# SlotCar_v1_0_1.net
KiCad netlist of a schematic drawn in EAGLE
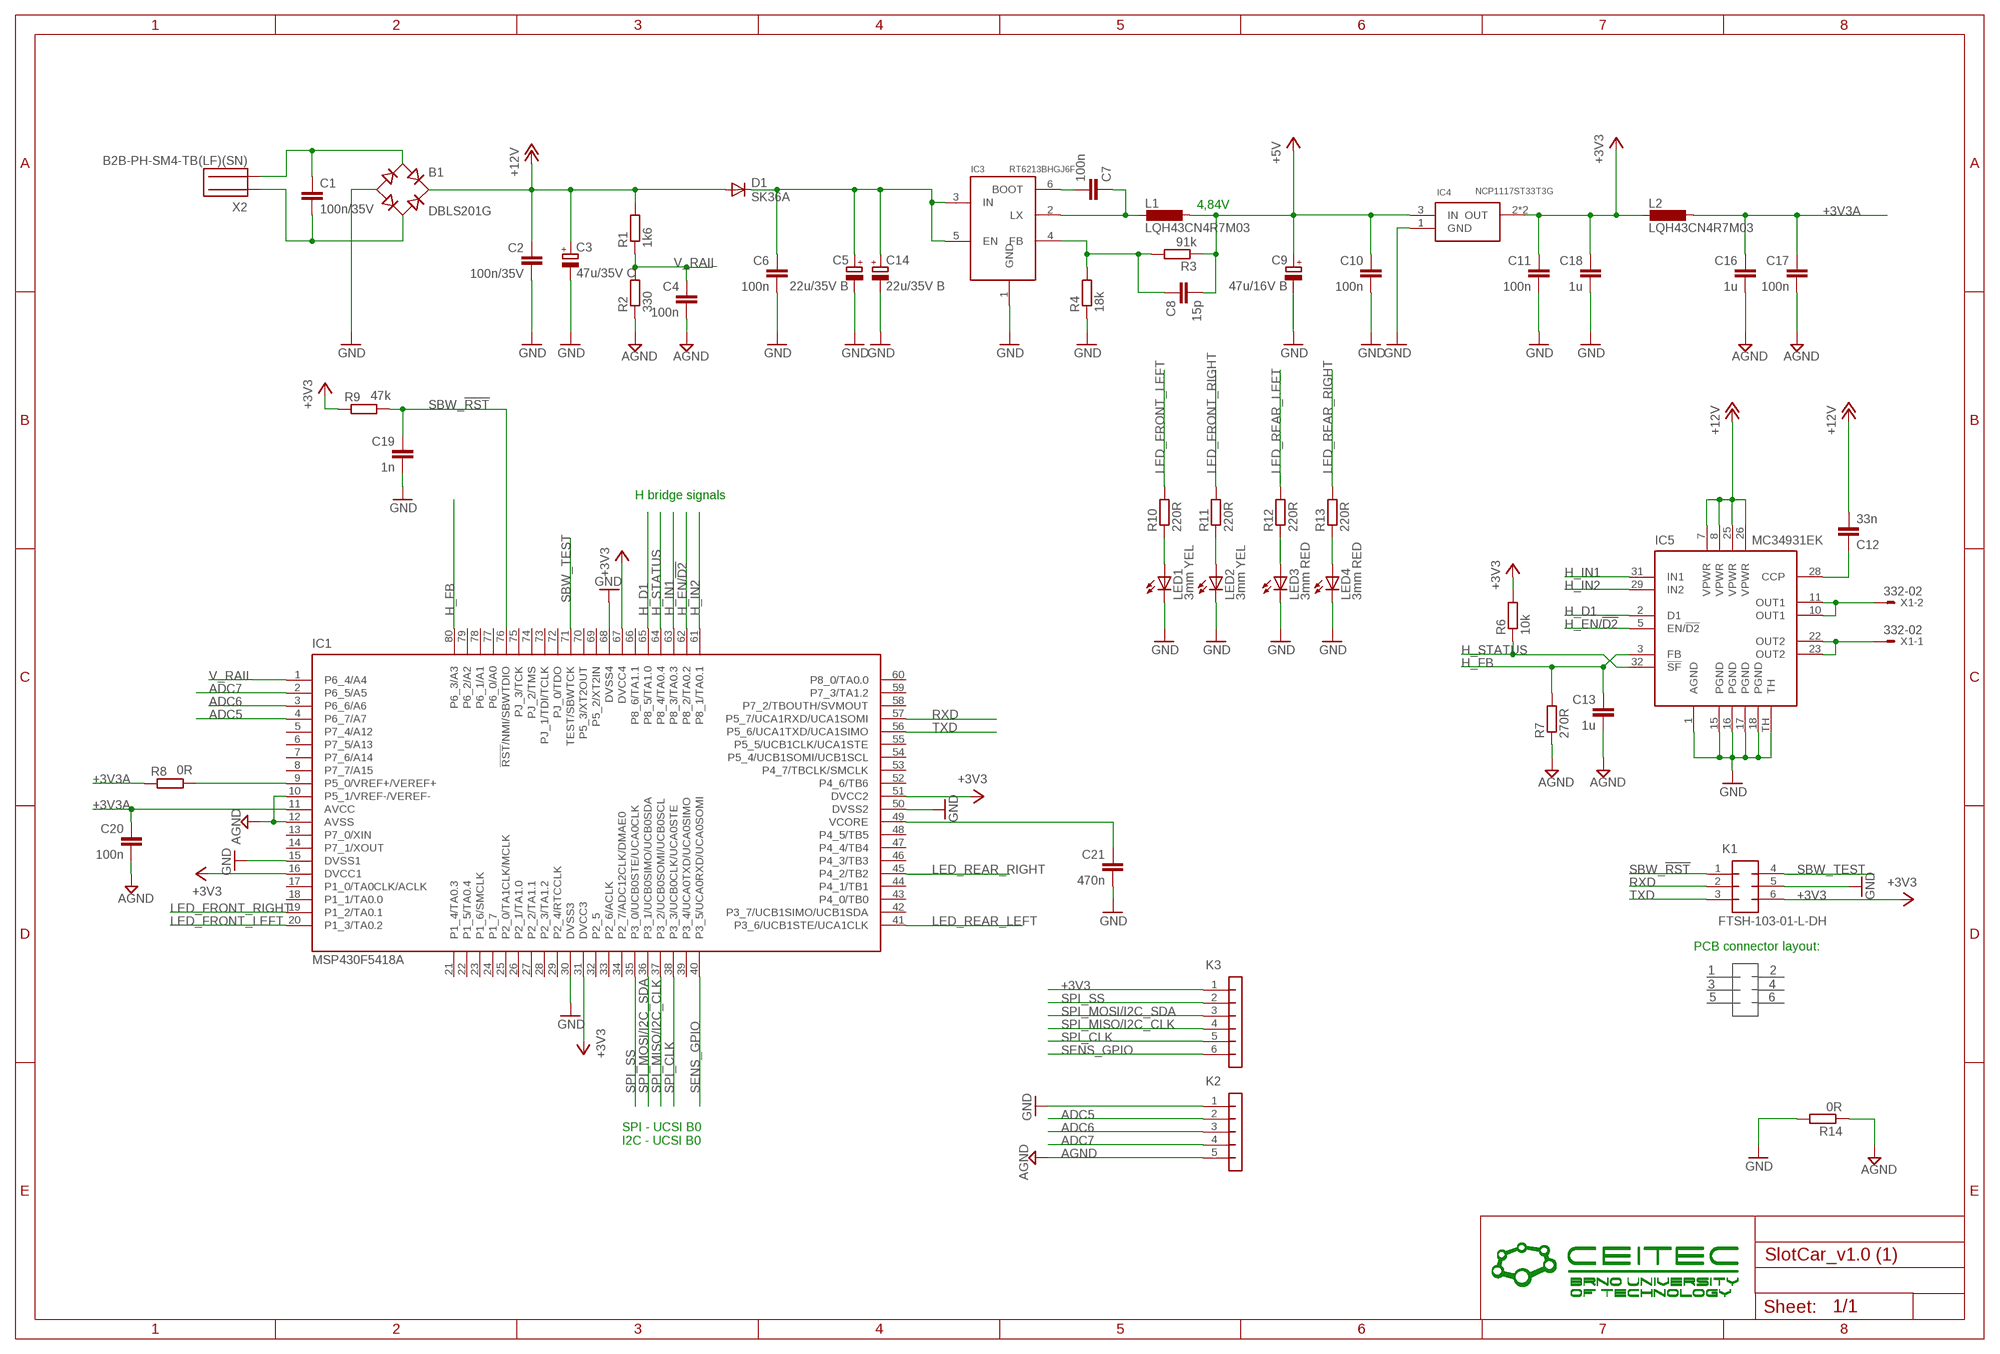
[diagram p0: schematic, sheet 1]

(export (version "E")
  (design (tool "Eeschema 10.0.6"))
  (components
    (comp (ref "B1")
      (value "DBLS201G")
      (footprint "eagle-import:DBS")
      (libsource (lib "eagle-import") (part "DB?GLS201"))
    )
    (comp (ref "C1")
      (value "100n/35V")
      (footprint "eagle-import:C0805K")
      (libsource (lib "eagle-import") (part "C-EUC0805K"))
    )
    (comp (ref "C2")
      (value "100n/35V")
      (footprint "eagle-import:C0805K")
      (libsource (lib "eagle-import") (part "C-EUC0805K"))
    )
    (comp (ref "C3")
      (value "47u/35V C")
      (footprint "eagle-import:153CLV-0505")
      (libsource (lib "eagle-import") (part "CPOL-EU153CLV-0505"))
    )
    (comp (ref "C4")
      (value "100n")
      (footprint "eagle-import:C0805K")
      (libsource (lib "eagle-import") (part "C-EUC0805K"))
    )
    (comp (ref "C5")
      (value "22u/35V B")
      (footprint "eagle-import:153CLV-0405")
      (libsource (lib "eagle-import") (part "CPOL-EU153CLV-0405"))
    )
    (comp (ref "C6")
      (value "100n")
      (footprint "eagle-import:C0805K")
      (libsource (lib "eagle-import") (part "C-EUC0805K"))
    )
    (comp (ref "C7")
      (value "100n")
      (footprint "eagle-import:C0805K")
      (libsource (lib "eagle-import") (part "C-EUC0805K"))
    )
    (comp (ref "C8")
      (value "15p")
      (footprint "eagle-import:C0805K")
      (libsource (lib "eagle-import") (part "C-EUC0805K"))
    )
    (comp (ref "C9")
      (value "47u/16V B")
      (footprint "eagle-import:153CLV-0405")
      (libsource (lib "eagle-import") (part "CPOL-EU153CLV-0405"))
    )
    (comp (ref "C10")
      (value "100n")
      (footprint "eagle-import:C0805K")
      (libsource (lib "eagle-import") (part "C-EUC0805K"))
    )
    (comp (ref "C11")
      (value "100n")
      (footprint "eagle-import:C0805K")
      (libsource (lib "eagle-import") (part "C-EUC0805K"))
    )
    (comp (ref "C12")
      (value "33n")
      (footprint "eagle-import:C0805K")
      (libsource (lib "eagle-import") (part "C-EUC0805K"))
    )
    (comp (ref "C13")
      (value "1u")
      (footprint "eagle-import:C0805K")
      (libsource (lib "eagle-import") (part "C-EUC0805K"))
    )
    (comp (ref "C14")
      (value "22u/35V B")
      (footprint "eagle-import:153CLV-0405")
      (libsource (lib "eagle-import") (part "CPOL-EU153CLV-0405"))
    )
    (comp (ref "C16")
      (value "1u")
      (footprint "eagle-import:C0805K")
      (libsource (lib "eagle-import") (part "C-EUC0805K"))
    )
    (comp (ref "C17")
      (value "100n")
      (footprint "eagle-import:C0805K")
      (libsource (lib "eagle-import") (part "C-EUC0805K"))
    )
    (comp (ref "C18")
      (value "1u")
      (footprint "eagle-import:C0805K")
      (libsource (lib "eagle-import") (part "C-EUC0805K"))
    )
    (comp (ref "C19")
      (value "1n")
      (footprint "eagle-import:C0805K")
      (libsource (lib "eagle-import") (part "C-EUC0805K"))
    )
    (comp (ref "C20")
      (value "100n")
      (footprint "eagle-import:C0805K")
      (libsource (lib "eagle-import") (part "C-EUC0805K"))
    )
    (comp (ref "C21")
      (value "470n")
      (footprint "eagle-import:C0805K")
      (libsource (lib "eagle-import") (part "C-EUC0805K"))
    )
    (comp (ref "D1")
      (value "SK36A")
      (footprint "eagle-import:DO214AC")
      (libsource (lib "eagle-import") (part "DIODE-DO214AC"))
    )
    (comp (ref "IC1")
      (value "MSP430F5418A")
      (footprint "eagle-import:PN_S-PQFP-G80")
      (fields (field (name "MPN") "MSP430F5418AIPN"))
      (libsource (lib "eagle-import") (part "MSP430F5418A"))
    )
    (comp (ref "IC3")
      (value "RT6213BHGJ6F")
      (footprint "eagle-import:SOT23-6")
      (libsource (lib "eagle-import") (part "RT6213BHGJ6F"))
    )
    (comp (ref "IC4")
      (value "NCP1117ST33T3G")
      (footprint "eagle-import:SOT223")
      (libsource (lib "eagle-import") (part "NCP1117ST33T3G"))
    )
    (comp (ref "IC5")
      (value "MC34931EK")
      (footprint "eagle-import:SOIC32W")
      (libsource (lib "eagle-import") (part "MC34931EK"))
    )
    (comp (ref "K1")
      (value "FTSH-103-01-L-DH")
      (footprint "eagle-import:PINHEAD_2X3_RM1.27")
      (libsource (lib "eagle-import") (part "FTSH-103-01-L-DH"))
    )
    (comp (ref "K2")
      (value "PIN_1X5_SMD")
      (footprint "eagle-import:PINHEAD_1X5_RM1.27SMD")
      (libsource (lib "eagle-import") (part "PIN_1X5_SMD"))
    )
    (comp (ref "K3")
      (value "PIN_1X6_SMD")
      (footprint "eagle-import:PINHEAD_1X6_RM1.27SMD")
      (libsource (lib "eagle-import") (part "PIN_1X6_SMD"))
    )
    (comp (ref "L1")
      (value "LQH43CN4R7M03")
      (footprint "eagle-import:L1812")
      (libsource (lib "eagle-import") (part "L-EUL1812"))
    )
    (comp (ref "L2")
      (value "LQH43CN4R7M03")
      (footprint "eagle-import:L1812")
      (libsource (lib "eagle-import") (part "L-EUL1812"))
    )
    (comp (ref "LED1")
      (value "3mm YEL")
      (footprint "eagle-import:LED3MM")
      (libsource (lib "eagle-import") (part "LED3MM"))
    )
    (comp (ref "LED2")
      (value "3mm YEL")
      (footprint "eagle-import:LED3MM")
      (libsource (lib "eagle-import") (part "LED3MM"))
    )
    (comp (ref "LED3")
      (value "3mm RED")
      (footprint "eagle-import:LED3MM")
      (libsource (lib "eagle-import") (part "LED3MM"))
    )
    (comp (ref "LED4")
      (value "3mm RED")
      (footprint "eagle-import:LED3MM")
      (libsource (lib "eagle-import") (part "LED3MM"))
    )
    (comp (ref "R1")
      (value "1k6")
      (footprint "eagle-import:M0805")
      (libsource (lib "eagle-import") (part "R-EU_M0805"))
    )
    (comp (ref "R2")
      (value "330")
      (footprint "eagle-import:M0805")
      (libsource (lib "eagle-import") (part "R-EU_M0805"))
    )
    (comp (ref "R3")
      (value "91k")
      (footprint "eagle-import:M0805")
      (libsource (lib "eagle-import") (part "R-EU_M0805"))
    )
    (comp (ref "R4")
      (value "18k")
      (footprint "eagle-import:M0805")
      (libsource (lib "eagle-import") (part "R-EU_M0805"))
    )
    (comp (ref "R6")
      (value "10k")
      (footprint "eagle-import:M0805")
      (libsource (lib "eagle-import") (part "R-EU_M0805"))
    )
    (comp (ref "R7")
      (value "270R")
      (footprint "eagle-import:M0805")
      (libsource (lib "eagle-import") (part "R-EU_M0805"))
    )
    (comp (ref "R8")
      (value "0R")
      (footprint "eagle-import:M0805")
      (libsource (lib "eagle-import") (part "R-EU_M0805"))
    )
    (comp (ref "R9")
      (value "47k")
      (footprint "eagle-import:M0805")
      (libsource (lib "eagle-import") (part "R-EU_M0805"))
    )
    (comp (ref "R10")
      (value "220R")
      (footprint "eagle-import:M0805")
      (libsource (lib "eagle-import") (part "R-EU_M0805"))
    )
    (comp (ref "R11")
      (value "220R")
      (footprint "eagle-import:M0805")
      (libsource (lib "eagle-import") (part "R-EU_M0805"))
    )
    (comp (ref "R12")
      (value "220R")
      (footprint "eagle-import:M0805")
      (libsource (lib "eagle-import") (part "R-EU_M0805"))
    )
    (comp (ref "R13")
      (value "220R")
      (footprint "eagle-import:M0805")
      (libsource (lib "eagle-import") (part "R-EU_M0805"))
    )
    (comp (ref "R14")
      (value "0R")
      (footprint "eagle-import:M0805")
      (libsource (lib "eagle-import") (part "R-EU_M0805"))
    )
    (comp (ref "X1")
      (value "332-02")
      (footprint "eagle-import:332-02")
      (libsource (lib "eagle-import") (part "332-02"))
    )
    (comp (ref "X2")
      (value "B2B-PH-SM4-TB(LF)(SN)")
      (footprint "eagle-import:JST-2.00MM-2P")
      (libsource (lib "eagle-import") (part "JST-2P-2.00MM-90DEG"))
    )
  )
  (nets
    (net (code "1") (name "+3V3") (class "Default")
      (node (ref "C11") (pin "1") (pinfunction "1_1") (pintype "passive"))
      (node (ref "C18") (pin "1") (pinfunction "1_1") (pintype "passive"))
      (node (ref "IC1") (pin "16") (pinfunction "DVCC1_16") (pintype "power_in"))
      (node (ref "IC1") (pin "31") (pinfunction "DVCC3_31") (pintype "power_in"))
      (node (ref "IC1") (pin "51") (pinfunction "DVCC2_51") (pintype "power_in"))
      (node (ref "IC1") (pin "67") (pinfunction "DVCC4_67") (pintype "power_in"))
      (node (ref "IC4") (pin "2") (pinfunction "OUT_2") (pintype "bidirectional"))
      (node (ref "IC4") (pin "4") (pinfunction "OUT_4") (pintype "bidirectional"))
      (node (ref "K1") (pin "6") (pinfunction "P$6_6") (pintype "bidirectional"))
      (node (ref "K3") (pin "1") (pinfunction "P$1_1") (pintype "bidirectional"))
      (node (ref "L2") (pin "2") (pinfunction "2_2") (pintype "passive"))
      (node (ref "R6") (pin "2") (pinfunction "2_2") (pintype "passive"))
      (node (ref "R9") (pin "1") (pinfunction "1_1") (pintype "passive"))
    )
    (net (code "2") (name "+5V") (class "Default")
      (node (ref "C10") (pin "1") (pinfunction "1_1") (pintype "passive"))
      (node (ref "C8") (pin "2") (pinfunction "2_2") (pintype "passive"))
      (node (ref "C9") (pin "+") (pinfunction "+_+") (pintype "passive"))
      (node (ref "IC4") (pin "3") (pinfunction "IN_3") (pintype "bidirectional"))
      (node (ref "L1") (pin "1") (pinfunction "1_1") (pintype "passive"))
      (node (ref "R3") (pin "1") (pinfunction "1_1") (pintype "passive"))
    )
    (net (code "3") (name "+12V") (class "Default")
      (node (ref "B1") (pin "+") (pinfunction "+_+") (pintype "passive"))
      (node (ref "C12") (pin "2") (pinfunction "2_2") (pintype "passive"))
      (node (ref "C2") (pin "1") (pinfunction "1_1") (pintype "passive"))
      (node (ref "C3") (pin "+") (pinfunction "+_+") (pintype "passive"))
      (node (ref "D1") (pin "A") (pinfunction "A_A") (pintype "passive"))
      (node (ref "IC5") (pin "25") (pinfunction "VPWR_25") (pintype "bidirectional"))
      (node (ref "IC5") (pin "26") (pinfunction "VPWR_26") (pintype "bidirectional"))
      (node (ref "IC5") (pin "7") (pinfunction "VPWR_7") (pintype "bidirectional"))
      (node (ref "IC5") (pin "8") (pinfunction "VPWR_8") (pintype "bidirectional"))
      (node (ref "R1") (pin "2") (pinfunction "2_2") (pintype "passive"))
    )
    (net (code "4") (name "/+3V3A") (class "Default")
      (node (ref "C16") (pin "1") (pinfunction "1_1") (pintype "passive"))
      (node (ref "C17") (pin "1") (pinfunction "1_1") (pintype "passive"))
      (node (ref "C20") (pin "1") (pinfunction "1_1") (pintype "passive"))
      (node (ref "IC1") (pin "11") (pinfunction "AVCC_11") (pintype "power_in"))
      (node (ref "L2") (pin "1") (pinfunction "1_1") (pintype "passive"))
      (node (ref "R8") (pin "1") (pinfunction "1_1") (pintype "passive"))
    )
    (net (code "5") (name "/ADC5") (class "Default")
      (node (ref "IC1") (pin "4") (pinfunction "P6_7/A7_4") (pintype "bidirectional"))
      (node (ref "K2") (pin "2") (pinfunction "P$2_2") (pintype "bidirectional"))
    )
    (net (code "6") (name "/ADC6") (class "Default")
      (node (ref "IC1") (pin "3") (pinfunction "P6_6/A6_3") (pintype "bidirectional"))
      (node (ref "K2") (pin "3") (pinfunction "P$3_3") (pintype "bidirectional"))
    )
    (net (code "7") (name "/ADC7") (class "Default")
      (node (ref "IC1") (pin "2") (pinfunction "P6_5/A5_2") (pintype "bidirectional"))
      (node (ref "K2") (pin "4") (pinfunction "P$4_4") (pintype "bidirectional"))
    )
    (net (code "8") (name "/H_D1") (class "Default")
      (node (ref "IC1") (pin "65") (pinfunction "P8_5/TA1.0_65") (pintype "bidirectional"))
      (node (ref "IC5") (pin "2") (pinfunction "D1_2") (pintype "bidirectional"))
    )
    (net (code "9") (name "/H_EN{slash}~{D2}") (class "Default")
      (node (ref "IC1") (pin "62") (pinfunction "P8_2/TA0.2_62") (pintype "bidirectional"))
      (node (ref "IC5") (pin "5") (pinfunction "EN/~{D2}_5") (pintype "bidirectional"))
    )
    (net (code "10") (name "/H_FB") (class "Default")
      (node (ref "C13") (pin "1") (pinfunction "1_1") (pintype "passive"))
      (node (ref "IC1") (pin "80") (pinfunction "P6_3/A3_80") (pintype "bidirectional"))
      (node (ref "IC5") (pin "3") (pinfunction "FB_3") (pintype "bidirectional"))
      (node (ref "R7") (pin "2") (pinfunction "2_2") (pintype "passive"))
    )
    (net (code "11") (name "/H_IN1") (class "Default")
      (node (ref "IC1") (pin "63") (pinfunction "P8_3/TA0.3_63") (pintype "bidirectional"))
      (node (ref "IC5") (pin "31") (pinfunction "IN1_31") (pintype "bidirectional"))
    )
    (net (code "12") (name "/H_IN2") (class "Default")
      (node (ref "IC1") (pin "61") (pinfunction "P8_1/TA0.1_61") (pintype "bidirectional"))
      (node (ref "IC5") (pin "29") (pinfunction "IN2_29") (pintype "bidirectional"))
    )
    (net (code "13") (name "/H_STATUS") (class "Default")
      (node (ref "IC1") (pin "64") (pinfunction "P8_4/TA0.4_64") (pintype "bidirectional"))
      (node (ref "IC5") (pin "32") (pinfunction "~{SF}_32") (pintype "bidirectional"))
      (node (ref "R6") (pin "1") (pinfunction "1_1") (pintype "passive"))
    )
    (net (code "14") (name "/LED_FRONT_LEFT") (class "Default")
      (node (ref "IC1") (pin "20") (pinfunction "P1_3/TA0.2_20") (pintype "bidirectional"))
      (node (ref "R10") (pin "2") (pinfunction "2_2") (pintype "passive"))
    )
    (net (code "15") (name "/LED_FRONT_RIGHT") (class "Default")
      (node (ref "IC1") (pin "19") (pinfunction "P1_2/TA0.1_19") (pintype "bidirectional"))
      (node (ref "R11") (pin "2") (pinfunction "2_2") (pintype "passive"))
    )
    (net (code "16") (name "/LED_REAR_LEFT") (class "Default")
      (node (ref "IC1") (pin "41") (pinfunction "P3_6/UCB1STE/UCA1CLK_41") (pintype "bidirectional"))
      (node (ref "R12") (pin "2") (pinfunction "2_2") (pintype "passive"))
    )
    (net (code "17") (name "/LED_REAR_RIGHT") (class "Default")
      (node (ref "IC1") (pin "45") (pinfunction "P4_2/TB2_45") (pintype "bidirectional"))
      (node (ref "R13") (pin "2") (pinfunction "2_2") (pintype "passive"))
    )
    (net (code "18") (name "/RXD") (class "Default")
      (node (ref "IC1") (pin "57") (pinfunction "P5_7/UCA1RXD/UCA1SOMI_57") (pintype "bidirectional"))
      (node (ref "K1") (pin "2") (pinfunction "P$2_2") (pintype "bidirectional"))
    )
    (net (code "19") (name "/SBW_TEST") (class "Default")
      (node (ref "IC1") (pin "71") (pinfunction "TEST/SBWTCK_71") (pintype "input"))
      (node (ref "K1") (pin "4") (pinfunction "P$4_4") (pintype "bidirectional"))
    )
    (net (code "20") (name "/SBW_~{RST}") (class "Default")
      (node (ref "C19") (pin "1") (pinfunction "1_1") (pintype "passive"))
      (node (ref "IC1") (pin "76") (pinfunction "~{RST}/NMI/SBWTDIO_76") (pintype "bidirectional"))
      (node (ref "K1") (pin "1") (pinfunction "P$1_1") (pintype "bidirectional"))
      (node (ref "R9") (pin "2") (pinfunction "2_2") (pintype "passive"))
    )
    (net (code "21") (name "/SENS_GPIO") (class "Default")
      (node (ref "IC1") (pin "40") (pinfunction "P3_5/UCA0RXD/UCA0SOMI_40") (pintype "bidirectional"))
      (node (ref "K3") (pin "6") (pinfunction "P$6_6") (pintype "bidirectional"))
    )
    (net (code "22") (name "/SPI_CLK") (class "Default")
      (node (ref "IC1") (pin "38") (pinfunction "P3_3/UCB0CLK/UCA0STE_38") (pintype "bidirectional"))
      (node (ref "K3") (pin "5") (pinfunction "P$5_5") (pintype "bidirectional"))
    )
    (net (code "23") (name "/SPI_MISO{slash}I2C_CLK") (class "Default")
      (node (ref "IC1") (pin "37") (pinfunction "P3_2/UCB0SOMI/UCB0SCL_37") (pintype "bidirectional"))
      (node (ref "K3") (pin "4") (pinfunction "P$4_4") (pintype "bidirectional"))
    )
    (net (code "24") (name "/SPI_MOSI{slash}I2C_SDA") (class "Default")
      (node (ref "IC1") (pin "36") (pinfunction "P3_1/UCB0SIMO/UCB0SDA_36") (pintype "bidirectional"))
      (node (ref "K3") (pin "3") (pinfunction "P$3_3") (pintype "bidirectional"))
    )
    (net (code "25") (name "/SPI_SS") (class "Default")
      (node (ref "IC1") (pin "35") (pinfunction "P3_0/UCB0STE/UCA0CLK_35") (pintype "bidirectional"))
      (node (ref "K3") (pin "2") (pinfunction "P$2_2") (pintype "bidirectional"))
    )
    (net (code "26") (name "/TXD") (class "Default")
      (node (ref "IC1") (pin "56") (pinfunction "P5_6/UCA1TXD/UCA1SIMO_56") (pintype "bidirectional"))
      (node (ref "K1") (pin "3") (pinfunction "P$3_3") (pintype "bidirectional"))
    )
    (net (code "27") (name "/V_RAIL") (class "Default")
      (node (ref "C4") (pin "1") (pinfunction "1_1") (pintype "passive"))
      (node (ref "IC1") (pin "1") (pinfunction "P6_4/A4_1") (pintype "bidirectional"))
      (node (ref "R1") (pin "1") (pinfunction "1_1") (pintype "passive"))
      (node (ref "R2") (pin "2") (pinfunction "2_2") (pintype "passive"))
    )
    (net (code "28") (name "AGND") (class "Default")
      (node (ref "C13") (pin "2") (pinfunction "2_2") (pintype "passive"))
      (node (ref "C16") (pin "2") (pinfunction "2_2") (pintype "passive"))
      (node (ref "C17") (pin "2") (pinfunction "2_2") (pintype "passive"))
      (node (ref "C20") (pin "2") (pinfunction "2_2") (pintype "passive"))
      (node (ref "C4") (pin "2") (pinfunction "2_2") (pintype "passive"))
      (node (ref "IC1") (pin "10") (pinfunction "P5_1/VREF-/VEREF-_10") (pintype "bidirectional"))
      (node (ref "IC1") (pin "12") (pinfunction "AVSS_12") (pintype "power_in"))
      (node (ref "K2") (pin "5") (pinfunction "P$5_5") (pintype "bidirectional"))
      (node (ref "R14") (pin "1") (pinfunction "1_1") (pintype "passive"))
      (node (ref "R2") (pin "1") (pinfunction "1_1") (pintype "passive"))
      (node (ref "R7") (pin "1") (pinfunction "1_1") (pintype "passive"))
    )
    (net (code "29") (name "GND") (class "Default")
      (node (ref "B1") (pin "-") (pinfunction "-_-") (pintype "passive"))
      (node (ref "C10") (pin "2") (pinfunction "2_2") (pintype "passive"))
      (node (ref "C11") (pin "2") (pinfunction "2_2") (pintype "passive"))
      (node (ref "C14") (pin "-") (pinfunction "-_-") (pintype "passive"))
      (node (ref "C18") (pin "2") (pinfunction "2_2") (pintype "passive"))
      (node (ref "C19") (pin "2") (pinfunction "2_2") (pintype "passive"))
      (node (ref "C2") (pin "2") (pinfunction "2_2") (pintype "passive"))
      (node (ref "C21") (pin "2") (pinfunction "2_2") (pintype "passive"))
      (node (ref "C3") (pin "-") (pinfunction "-_-") (pintype "passive"))
      (node (ref "C5") (pin "-") (pinfunction "-_-") (pintype "passive"))
      (node (ref "C6") (pin "2") (pinfunction "2_2") (pintype "passive"))
      (node (ref "C9") (pin "-") (pinfunction "-_-") (pintype "passive"))
      (node (ref "IC1") (pin "15") (pinfunction "DVSS1_15") (pintype "power_in"))
      (node (ref "IC1") (pin "30") (pinfunction "DVSS3_30") (pintype "power_in"))
      (node (ref "IC1") (pin "50") (pinfunction "DVSS2_50") (pintype "power_in"))
      (node (ref "IC1") (pin "68") (pinfunction "DVSS4_68") (pintype "power_in"))
      (node (ref "IC3") (pin "1") (pinfunction "GND_1") (pintype "bidirectional"))
      (node (ref "IC4") (pin "1") (pinfunction "GND_1") (pintype "bidirectional"))
      (node (ref "IC5") (pin "1") (pinfunction "AGND_1") (pintype "bidirectional"))
      (node (ref "IC5") (pin "15") (pinfunction "PGND_15") (pintype "bidirectional"))
      (node (ref "IC5") (pin "16") (pinfunction "PGND_16") (pintype "bidirectional"))
      (node (ref "IC5") (pin "17") (pinfunction "PGND_17") (pintype "bidirectional"))
      (node (ref "IC5") (pin "18") (pinfunction "PGND_18") (pintype "bidirectional"))
      (node (ref "IC5") (pin "TH") (pinfunction "TH_TH") (pintype "bidirectional"))
      (node (ref "K1") (pin "5") (pinfunction "P$5_5") (pintype "bidirectional"))
      (node (ref "K2") (pin "1") (pinfunction "P$1_1") (pintype "bidirectional"))
      (node (ref "LED1") (pin "K") (pinfunction "C_K") (pintype "passive"))
      (node (ref "LED2") (pin "K") (pinfunction "C_K") (pintype "passive"))
      (node (ref "LED3") (pin "K") (pinfunction "C_K") (pintype "passive"))
      (node (ref "LED4") (pin "K") (pinfunction "C_K") (pintype "passive"))
      (node (ref "R14") (pin "2") (pinfunction "2_2") (pintype "passive"))
      (node (ref "R4") (pin "1") (pinfunction "1_1") (pintype "passive"))
    )
    (net (code "30") (name "Net-(IC1-P5_0{slash}VREF+{slash}VEREF+)") (class "Default")
      (node (ref "IC1") (pin "9") (pinfunction "P5_0/VREF+/VEREF+_9") (pintype "bidirectional"))
      (node (ref "R8") (pin "2") (pinfunction "2_2") (pintype "passive"))
    )
    (net (code "31") (name "Net-(IC1-VCORE)") (class "Default")
      (node (ref "C21") (pin "1") (pinfunction "1_1") (pintype "passive"))
      (node (ref "IC1") (pin "49") (pinfunction "VCORE_49") (pintype "power_in"))
    )
    (net (code "32") (name "Net-(IC3-BOOT)") (class "Default")
      (node (ref "C7") (pin "2") (pinfunction "2_2") (pintype "passive"))
      (node (ref "IC3") (pin "6") (pinfunction "BOOT_6") (pintype "bidirectional"))
    )
    (net (code "33") (name "Net-(IC3-EN)") (class "Default")
      (node (ref "C14") (pin "+") (pinfunction "+_+") (pintype "passive"))
      (node (ref "C5") (pin "+") (pinfunction "+_+") (pintype "passive"))
      (node (ref "C6") (pin "1") (pinfunction "1_1") (pintype "passive"))
      (node (ref "D1") (pin "C") (pinfunction "C_C") (pintype "passive"))
      (node (ref "IC3") (pin "3") (pinfunction "IN_3") (pintype "bidirectional"))
      (node (ref "IC3") (pin "5") (pinfunction "EN_5") (pintype "bidirectional"))
    )
    (net (code "34") (name "Net-(IC3-FB)") (class "Default")
      (node (ref "C8") (pin "1") (pinfunction "1_1") (pintype "passive"))
      (node (ref "IC3") (pin "4") (pinfunction "FB_4") (pintype "bidirectional"))
      (node (ref "R3") (pin "2") (pinfunction "2_2") (pintype "passive"))
      (node (ref "R4") (pin "2") (pinfunction "2_2") (pintype "passive"))
    )
    (net (code "35") (name "Net-(IC3-LX)") (class "Default")
      (node (ref "C7") (pin "1") (pinfunction "1_1") (pintype "passive"))
      (node (ref "IC3") (pin "2") (pinfunction "LX_2") (pintype "bidirectional"))
      (node (ref "L1") (pin "2") (pinfunction "2_2") (pintype "passive"))
    )
    (net (code "36") (name "Net-(IC5-CCP)") (class "Default")
      (node (ref "C12") (pin "1") (pinfunction "1_1") (pintype "passive"))
      (node (ref "IC5") (pin "28") (pinfunction "CCP_28") (pintype "bidirectional"))
    )
    (net (code "37") (name "Net-(LED1-PadA)") (class "Default")
      (node (ref "LED1") (pin "A") (pinfunction "A_A") (pintype "passive"))
      (node (ref "R10") (pin "1") (pinfunction "1_1") (pintype "passive"))
    )
    (net (code "38") (name "Net-(LED2-PadA)") (class "Default")
      (node (ref "LED2") (pin "A") (pinfunction "A_A") (pintype "passive"))
      (node (ref "R11") (pin "1") (pinfunction "1_1") (pintype "passive"))
    )
    (net (code "39") (name "Net-(LED3-PadA)") (class "Default")
      (node (ref "LED3") (pin "A") (pinfunction "A_A") (pintype "passive"))
      (node (ref "R12") (pin "1") (pinfunction "1_1") (pintype "passive"))
    )
    (net (code "40") (name "Net-(LED4-PadA)") (class "Default")
      (node (ref "LED4") (pin "A") (pinfunction "A_A") (pintype "passive"))
      (node (ref "R13") (pin "1") (pinfunction "1_1") (pintype "passive"))
    )
    (net (code "41") (name "Net-(X1A-S)") (class "Default")
      (node (ref "IC5") (pin "22") (pinfunction "OUT2_22") (pintype "bidirectional"))
      (node (ref "IC5") (pin "23") (pinfunction "OUT2_23") (pintype "bidirectional"))
      (node (ref "X1") (pin "1") (pinfunction "S_1") (pintype "passive"))
    )
    (net (code "42") (name "Net-(X1B-S)") (class "Default")
      (node (ref "IC5") (pin "10") (pinfunction "OUT1_10") (pintype "bidirectional"))
      (node (ref "IC5") (pin "11") (pinfunction "OUT1_11") (pintype "bidirectional"))
      (node (ref "X1") (pin "2") (pinfunction "S_2") (pintype "passive"))
    )
    (net (code "43") (name "Net-(X2-P$1)") (class "Default")
      (node (ref "B1") (pin "AC2") (pinfunction "AC2_AC2") (pintype "passive"))
      (node (ref "C1") (pin "2") (pinfunction "2_2") (pintype "passive"))
      (node (ref "X2") (pin "1") (pinfunction "P$1_1") (pintype "bidirectional"))
    )
    (net (code "44") (name "Net-(X2-P$2)") (class "Default")
      (node (ref "B1") (pin "AC1") (pinfunction "AC1_AC1") (pintype "passive"))
      (node (ref "C1") (pin "1") (pinfunction "1_1") (pintype "passive"))
      (node (ref "X2") (pin "2") (pinfunction "P$2_2") (pintype "bidirectional"))
    )
    (net (code "45") (name "unconnected-(IC1-P1_0{slash}TA0CLK{slash}ACLK-Pad17)") (class "Default")
      (node (ref "IC1") (pin "17") (pinfunction "P1_0/TA0CLK/ACLK_17") (pintype "bidirectional"))
    )
    (net (code "46") (name "unconnected-(IC1-P1_1{slash}TA0.0-Pad18)") (class "Default")
      (node (ref "IC1") (pin "18") (pinfunction "P1_1/TA0.0_18") (pintype "bidirectional"))
    )
    (net (code "47") (name "unconnected-(IC1-P1_4{slash}TA0.3-Pad21)") (class "Default")
      (node (ref "IC1") (pin "21") (pinfunction "P1_4/TA0.3_21") (pintype "bidirectional"))
    )
    (net (code "48") (name "unconnected-(IC1-P1_5{slash}TA0.4-Pad22)") (class "Default")
      (node (ref "IC1") (pin "22") (pinfunction "P1_5/TA0.4_22") (pintype "bidirectional"))
    )
    (net (code "49") (name "unconnected-(IC1-P1_6{slash}SMCLK-Pad23)") (class "Default")
      (node (ref "IC1") (pin "23") (pinfunction "P1_6/SMCLK_23") (pintype "bidirectional"))
    )
    (net (code "50") (name "unconnected-(IC1-P1_7-Pad24)") (class "Default")
      (node (ref "IC1") (pin "24") (pinfunction "P1_7_24") (pintype "bidirectional"))
    )
    (net (code "51") (name "unconnected-(IC1-P2_0{slash}TA1CLK{slash}MCLK-Pad25)") (class "Default")
      (node (ref "IC1") (pin "25") (pinfunction "P2_0/TA1CLK/MCLK_25") (pintype "bidirectional"))
    )
    (net (code "52") (name "unconnected-(IC1-P2_1{slash}TA1.0-Pad26)") (class "Default")
      (node (ref "IC1") (pin "26") (pinfunction "P2_1/TA1.0_26") (pintype "bidirectional"))
    )
    (net (code "53") (name "unconnected-(IC1-P2_2{slash}TA1.1-Pad27)") (class "Default")
      (node (ref "IC1") (pin "27") (pinfunction "P2_2/TA1.1_27") (pintype "bidirectional"))
    )
    (net (code "54") (name "unconnected-(IC1-P2_3{slash}TA1.2-Pad28)") (class "Default")
      (node (ref "IC1") (pin "28") (pinfunction "P2_3/TA1.2_28") (pintype "bidirectional"))
    )
    (net (code "55") (name "unconnected-(IC1-P2_4{slash}RTCCLK-Pad29)") (class "Default")
      (node (ref "IC1") (pin "29") (pinfunction "P2_4/RTCCLK_29") (pintype "bidirectional"))
    )
    (net (code "56") (name "unconnected-(IC1-P2_5-Pad32)") (class "Default")
      (node (ref "IC1") (pin "32") (pinfunction "P2_5_32") (pintype "bidirectional"))
    )
    (net (code "57") (name "unconnected-(IC1-P2_6{slash}ACLK-Pad33)") (class "Default")
      (node (ref "IC1") (pin "33") (pinfunction "P2_6/ACLK_33") (pintype "bidirectional"))
    )
    (net (code "58") (name "unconnected-(IC1-P2_7{slash}ADC12CLK{slash}DMAE0-Pad34)") (class "Default")
      (node (ref "IC1") (pin "34") (pinfunction "P2_7/ADC12CLK/DMAE0_34") (pintype "bidirectional"))
    )
    (net (code "59") (name "unconnected-(IC1-P3_4{slash}UCA0TXD{slash}UCA0SIMO-Pad39)") (class "Default")
      (node (ref "IC1") (pin "39") (pinfunction "P3_4/UCA0TXD/UCA0SIMO_39") (pintype "bidirectional"))
    )
    (net (code "60") (name "unconnected-(IC1-P3_7{slash}UCB1SIMO{slash}UCB1SDA-Pad42)") (class "Default")
      (node (ref "IC1") (pin "42") (pinfunction "P3_7/UCB1SIMO/UCB1SDA_42") (pintype "bidirectional"))
    )
    (net (code "61") (name "unconnected-(IC1-P4_0{slash}TB0-Pad43)") (class "Default")
      (node (ref "IC1") (pin "43") (pinfunction "P4_0/TB0_43") (pintype "bidirectional"))
    )
    (net (code "62") (name "unconnected-(IC1-P4_1{slash}TB1-Pad44)") (class "Default")
      (node (ref "IC1") (pin "44") (pinfunction "P4_1/TB1_44") (pintype "bidirectional"))
    )
    (net (code "63") (name "unconnected-(IC1-P4_3{slash}TB3-Pad46)") (class "Default")
      (node (ref "IC1") (pin "46") (pinfunction "P4_3/TB3_46") (pintype "bidirectional"))
    )
    (net (code "64") (name "unconnected-(IC1-P4_4{slash}TB4-Pad47)") (class "Default")
      (node (ref "IC1") (pin "47") (pinfunction "P4_4/TB4_47") (pintype "bidirectional"))
    )
    (net (code "65") (name "unconnected-(IC1-P4_5{slash}TB5-Pad48)") (class "Default")
      (node (ref "IC1") (pin "48") (pinfunction "P4_5/TB5_48") (pintype "bidirectional"))
    )
    (net (code "66") (name "unconnected-(IC1-P4_6{slash}TB6-Pad52)") (class "Default")
      (node (ref "IC1") (pin "52") (pinfunction "P4_6/TB6_52") (pintype "bidirectional"))
    )
    (net (code "67") (name "unconnected-(IC1-P4_7{slash}TBCLK{slash}SMCLK-Pad53)") (class "Default")
      (node (ref "IC1") (pin "53") (pinfunction "P4_7/TBCLK/SMCLK_53") (pintype "bidirectional"))
    )
    (net (code "68") (name "unconnected-(IC1-P5_2{slash}XT2IN-Pad69)") (class "Default")
      (node (ref "IC1") (pin "69") (pinfunction "P5_2/XT2IN_69") (pintype "bidirectional"))
    )
    (net (code "69") (name "unconnected-(IC1-P5_3{slash}XT2OUT-Pad70)") (class "Default")
      (node (ref "IC1") (pin "70") (pinfunction "P5_3/XT2OUT_70") (pintype "bidirectional"))
    )
    (net (code "70") (name "unconnected-(IC1-P5_4{slash}UCB1SOMI{slash}UCB1SCL-Pad54)") (class "Default")
      (node (ref "IC1") (pin "54") (pinfunction "P5_4/UCB1SOMI/UCB1SCL_54") (pintype "bidirectional"))
    )
    (net (code "71") (name "unconnected-(IC1-P5_5{slash}UCB1CLK{slash}UCA1STE-Pad55)") (class "Default")
      (node (ref "IC1") (pin "55") (pinfunction "P5_5/UCB1CLK/UCA1STE_55") (pintype "bidirectional"))
    )
    (net (code "72") (name "unconnected-(IC1-P6_0{slash}A0-Pad77)") (class "Default")
      (node (ref "IC1") (pin "77") (pinfunction "P6_0/A0_77") (pintype "bidirectional"))
    )
    (net (code "73") (name "unconnected-(IC1-P6_1{slash}A1-Pad78)") (class "Default")
      (node (ref "IC1") (pin "78") (pinfunction "P6_1/A1_78") (pintype "bidirectional"))
    )
    (net (code "74") (name "unconnected-(IC1-P6_2{slash}A2-Pad79)") (class "Default")
      (node (ref "IC1") (pin "79") (pinfunction "P6_2/A2_79") (pintype "bidirectional"))
    )
    (net (code "75") (name "unconnected-(IC1-P7_0{slash}XIN-Pad13)") (class "Default")
      (node (ref "IC1") (pin "13") (pinfunction "P7_0/XIN_13") (pintype "bidirectional"))
    )
    (net (code "76") (name "unconnected-(IC1-P7_1{slash}XOUT-Pad14)") (class "Default")
      (node (ref "IC1") (pin "14") (pinfunction "P7_1/XOUT_14") (pintype "bidirectional"))
    )
    (net (code "77") (name "unconnected-(IC1-P7_2{slash}TBOUTH{slash}SVMOUT-Pad58)") (class "Default")
      (node (ref "IC1") (pin "58") (pinfunction "P7_2/TBOUTH/SVMOUT_58") (pintype "bidirectional"))
    )
    (net (code "78") (name "unconnected-(IC1-P7_3{slash}TA1.2-Pad59)") (class "Default")
      (node (ref "IC1") (pin "59") (pinfunction "P7_3/TA1.2_59") (pintype "bidirectional"))
    )
    (net (code "79") (name "unconnected-(IC1-P7_4{slash}A12-Pad5)") (class "Default")
      (node (ref "IC1") (pin "5") (pinfunction "P7_4/A12_5") (pintype "bidirectional"))
    )
    (net (code "80") (name "unconnected-(IC1-P7_5{slash}A13-Pad6)") (class "Default")
      (node (ref "IC1") (pin "6") (pinfunction "P7_5/A13_6") (pintype "bidirectional"))
    )
    (net (code "81") (name "unconnected-(IC1-P7_6{slash}A14-Pad7)") (class "Default")
      (node (ref "IC1") (pin "7") (pinfunction "P7_6/A14_7") (pintype "bidirectional"))
    )
    (net (code "82") (name "unconnected-(IC1-P7_7{slash}A15-Pad8)") (class "Default")
      (node (ref "IC1") (pin "8") (pinfunction "P7_7/A15_8") (pintype "bidirectional"))
    )
    (net (code "83") (name "unconnected-(IC1-P8_0{slash}TA0.0-Pad60)") (class "Default")
      (node (ref "IC1") (pin "60") (pinfunction "P8_0/TA0.0_60") (pintype "bidirectional"))
    )
    (net (code "84") (name "unconnected-(IC1-P8_6{slash}TA1.1-Pad66)") (class "Default")
      (node (ref "IC1") (pin "66") (pinfunction "P8_6/TA1.1_66") (pintype "bidirectional"))
    )
    (net (code "85") (name "unconnected-(IC1-PJ_0{slash}TDO-Pad72)") (class "Default")
      (node (ref "IC1") (pin "72") (pinfunction "PJ_0/TDO_72") (pintype "bidirectional"))
    )
    (net (code "86") (name "unconnected-(IC1-PJ_1{slash}TDI{slash}TCLK-Pad73)") (class "Default")
      (node (ref "IC1") (pin "73") (pinfunction "PJ_1/TDI/TCLK_73") (pintype "bidirectional"))
    )
    (net (code "87") (name "unconnected-(IC1-PJ_2{slash}TMS-Pad74)") (class "Default")
      (node (ref "IC1") (pin "74") (pinfunction "PJ_2/TMS_74") (pintype "bidirectional"))
    )
    (net (code "88") (name "unconnected-(IC1-PJ_3{slash}TCK-Pad75)") (class "Default")
      (node (ref "IC1") (pin "75") (pinfunction "PJ_3/TCK_75") (pintype "bidirectional"))
    )
  )
)
